# 01_Power.net
KiCad netlist of a schematic drawn in Altium Designer
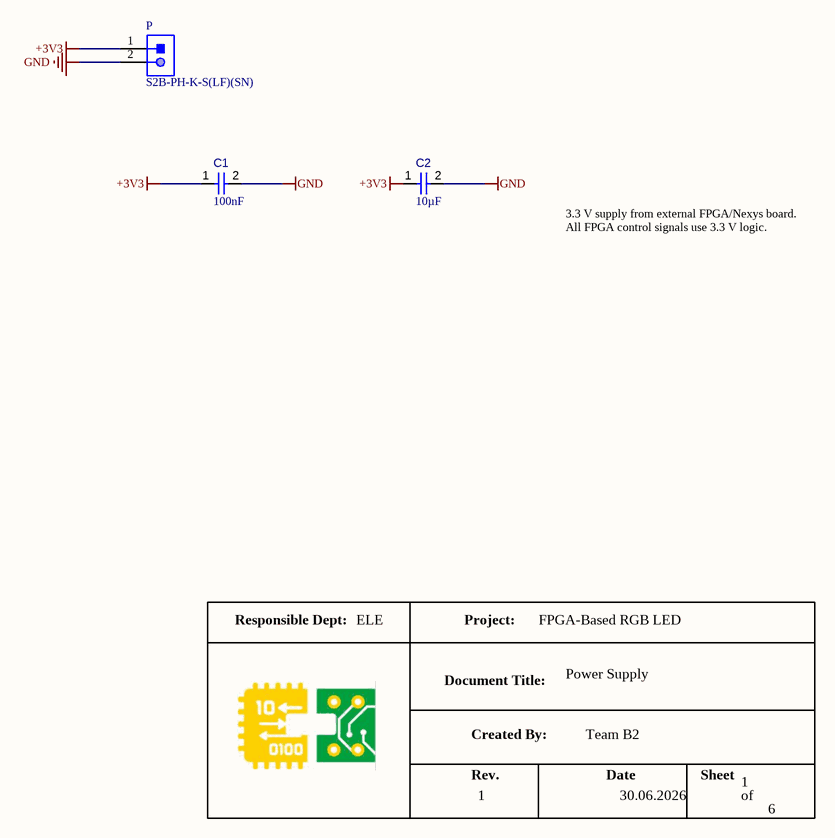
[diagram p0: 01_Power.SchDoc]

(export (version "E")
  (design (tool "Eeschema 10.0.6"))
  (components
    (comp (ref "C1")
      (value "100nF")
      (footprint "CAPC2013X95X50LL10T25")
      (description "Chip Capacitor, 100 nF, +/- 10%, 50 V, 0805 (2012 Metric)")
      (fields (field (name "TOLERANCE") "10%") (field (name "Comment") "Capacitor 100 nF +/-10% 50 V 0805"))
      (libsource (lib "Hany Chowdhury") (part "CAP-NP-2"))
    )
    (comp (ref "C2")
      (value "10µF")
      (footprint "CAPC0805(2012)145_L")
      (description "Chip Capacitor, 10µF +/-20%, 25V, 0805, Thickness 1.45 mm")
      (fields (field (name "TOLERANCE") "10%") (field (name "Comment") "Capacitor 10µF +/-20% 25V 0805"))
      (libsource (lib "Hany Chowdhury") (part "CAP-NP-2"))
    )
    (comp (ref "P")
      (value "S2B-PH-K-S(LF)(SN)")
      (footprint "JST-S2B-PH-K-S_V")
      (fields (field (name "TOLERANCE") "20%"))
      (libsource (lib "Altium Content Vault") (part "CN-1P-M-R2"))
    )
  )
  (nets
    (net (code "1") (name "+3V3") (class "Default")
      (node (ref "C1") (pin "1") (pinfunction "1_1") (pintype "passive"))
      (node (ref "C2") (pin "1") (pinfunction "1_1") (pintype "passive"))
      (node (ref "P") (pin "1") (pinfunction "1_1") (pintype "passive"))
    )
    (net (code "2") (name "GND") (class "Default")
      (node (ref "C1") (pin "2") (pinfunction "2_2") (pintype "passive"))
      (node (ref "C2") (pin "2") (pinfunction "2_2") (pintype "passive"))
      (node (ref "P") (pin "2") (pinfunction "2_2") (pintype "passive"))
    )
  )
)
